# FlightController.net
KiCad netlist of a schematic drawn in Altium Designer
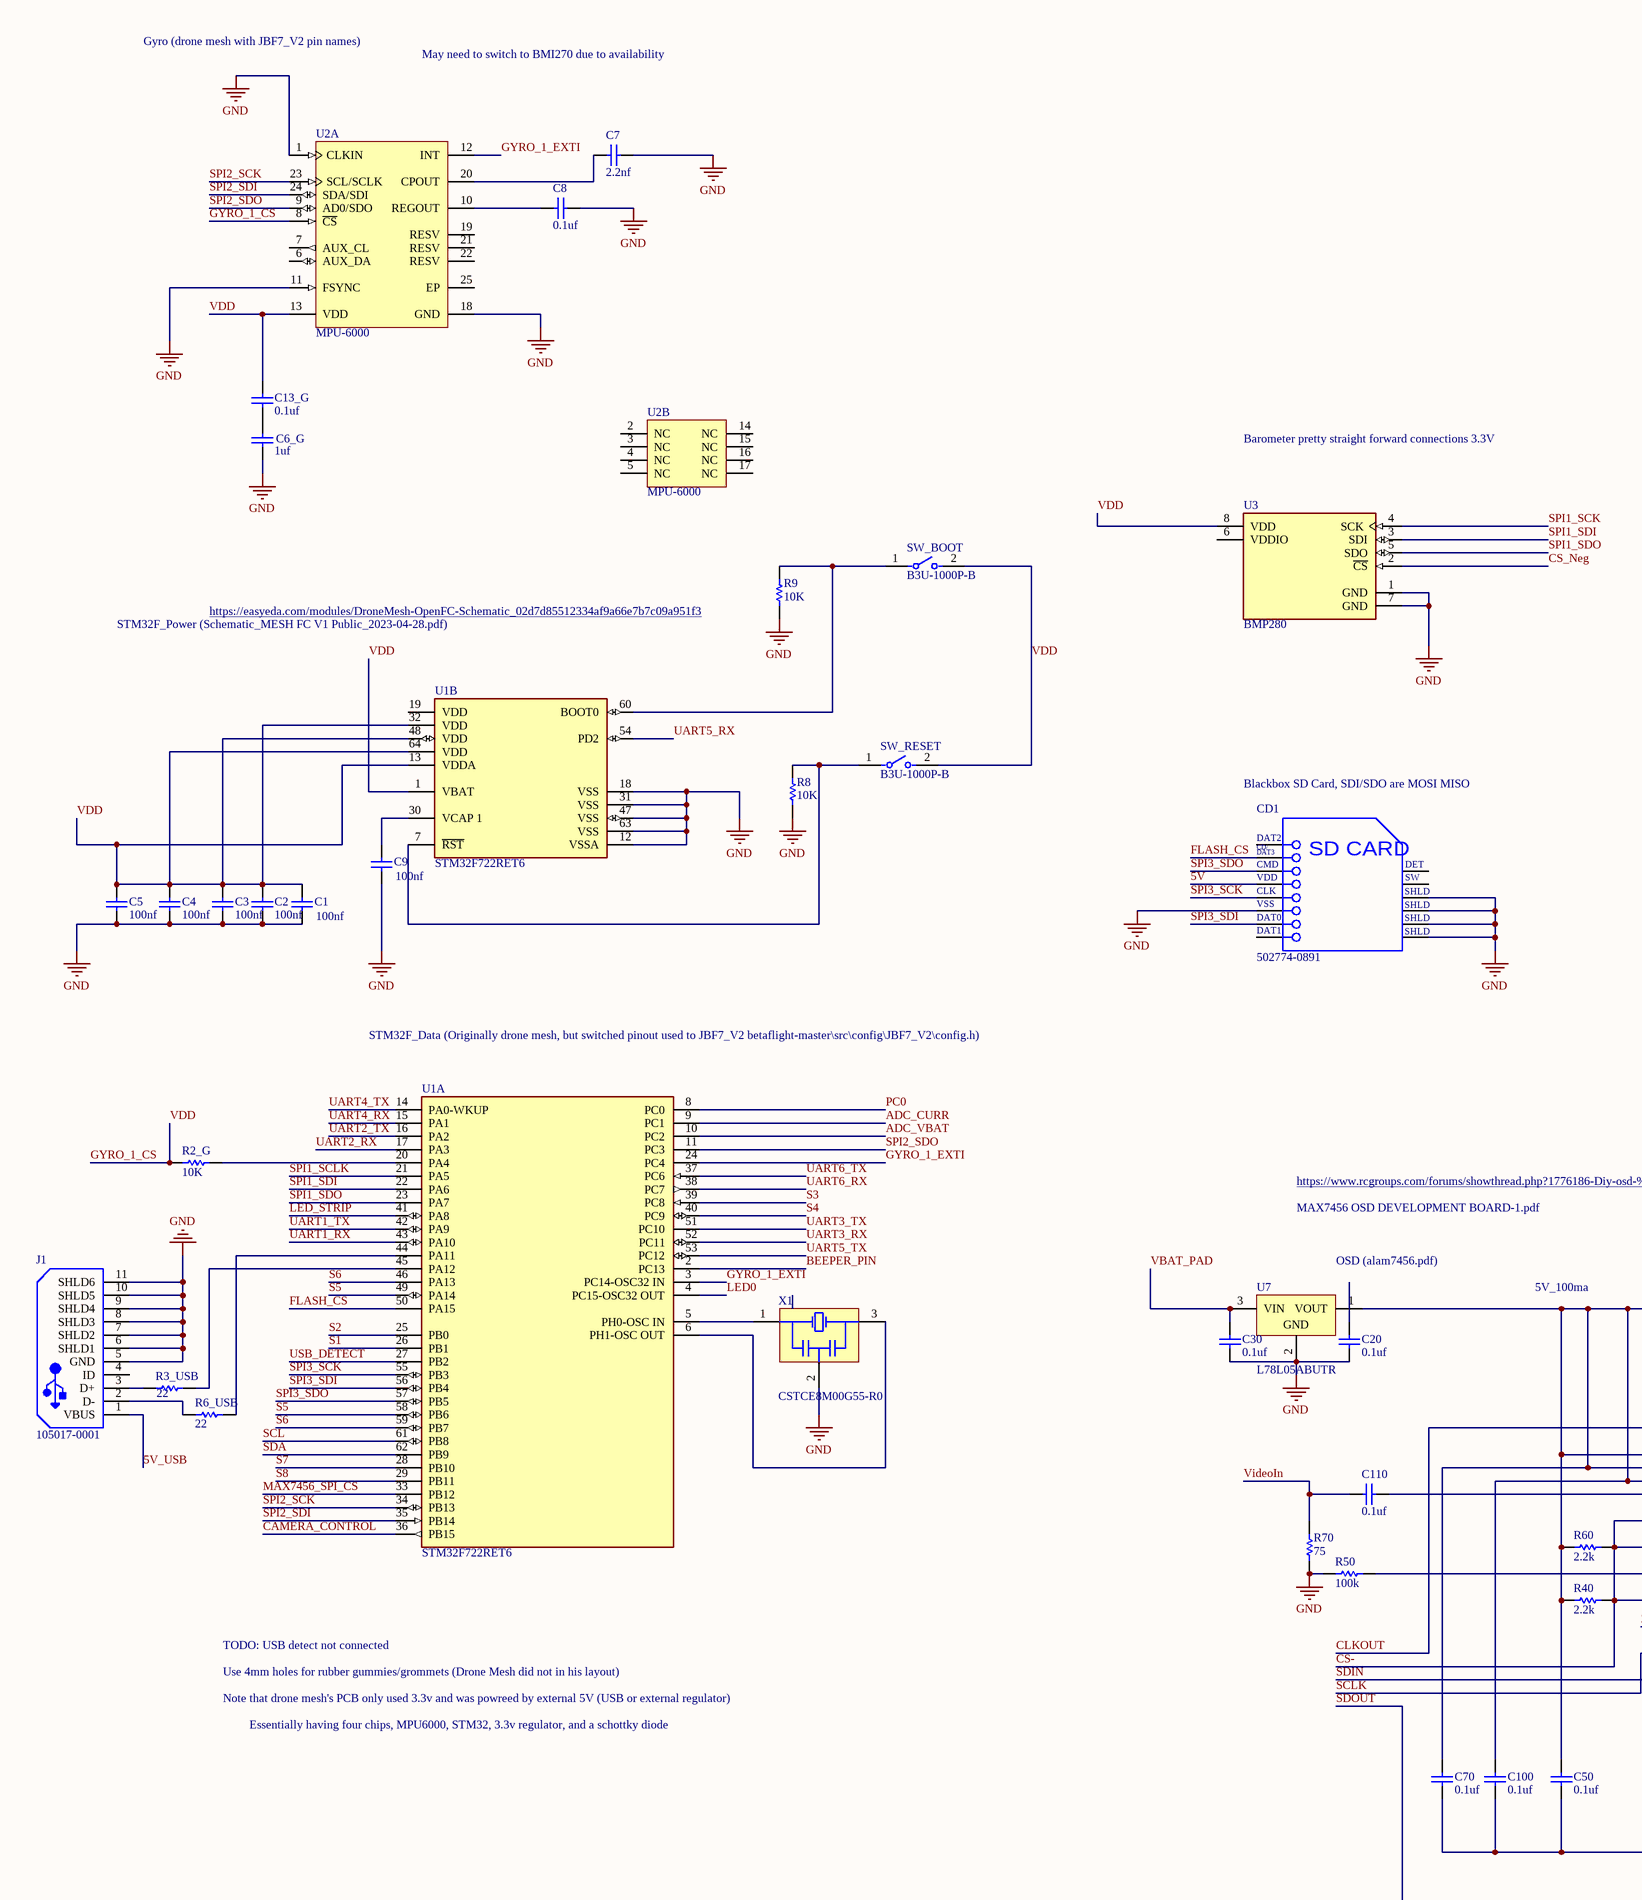
[diagram p0: FlightController.SchDoc, left]
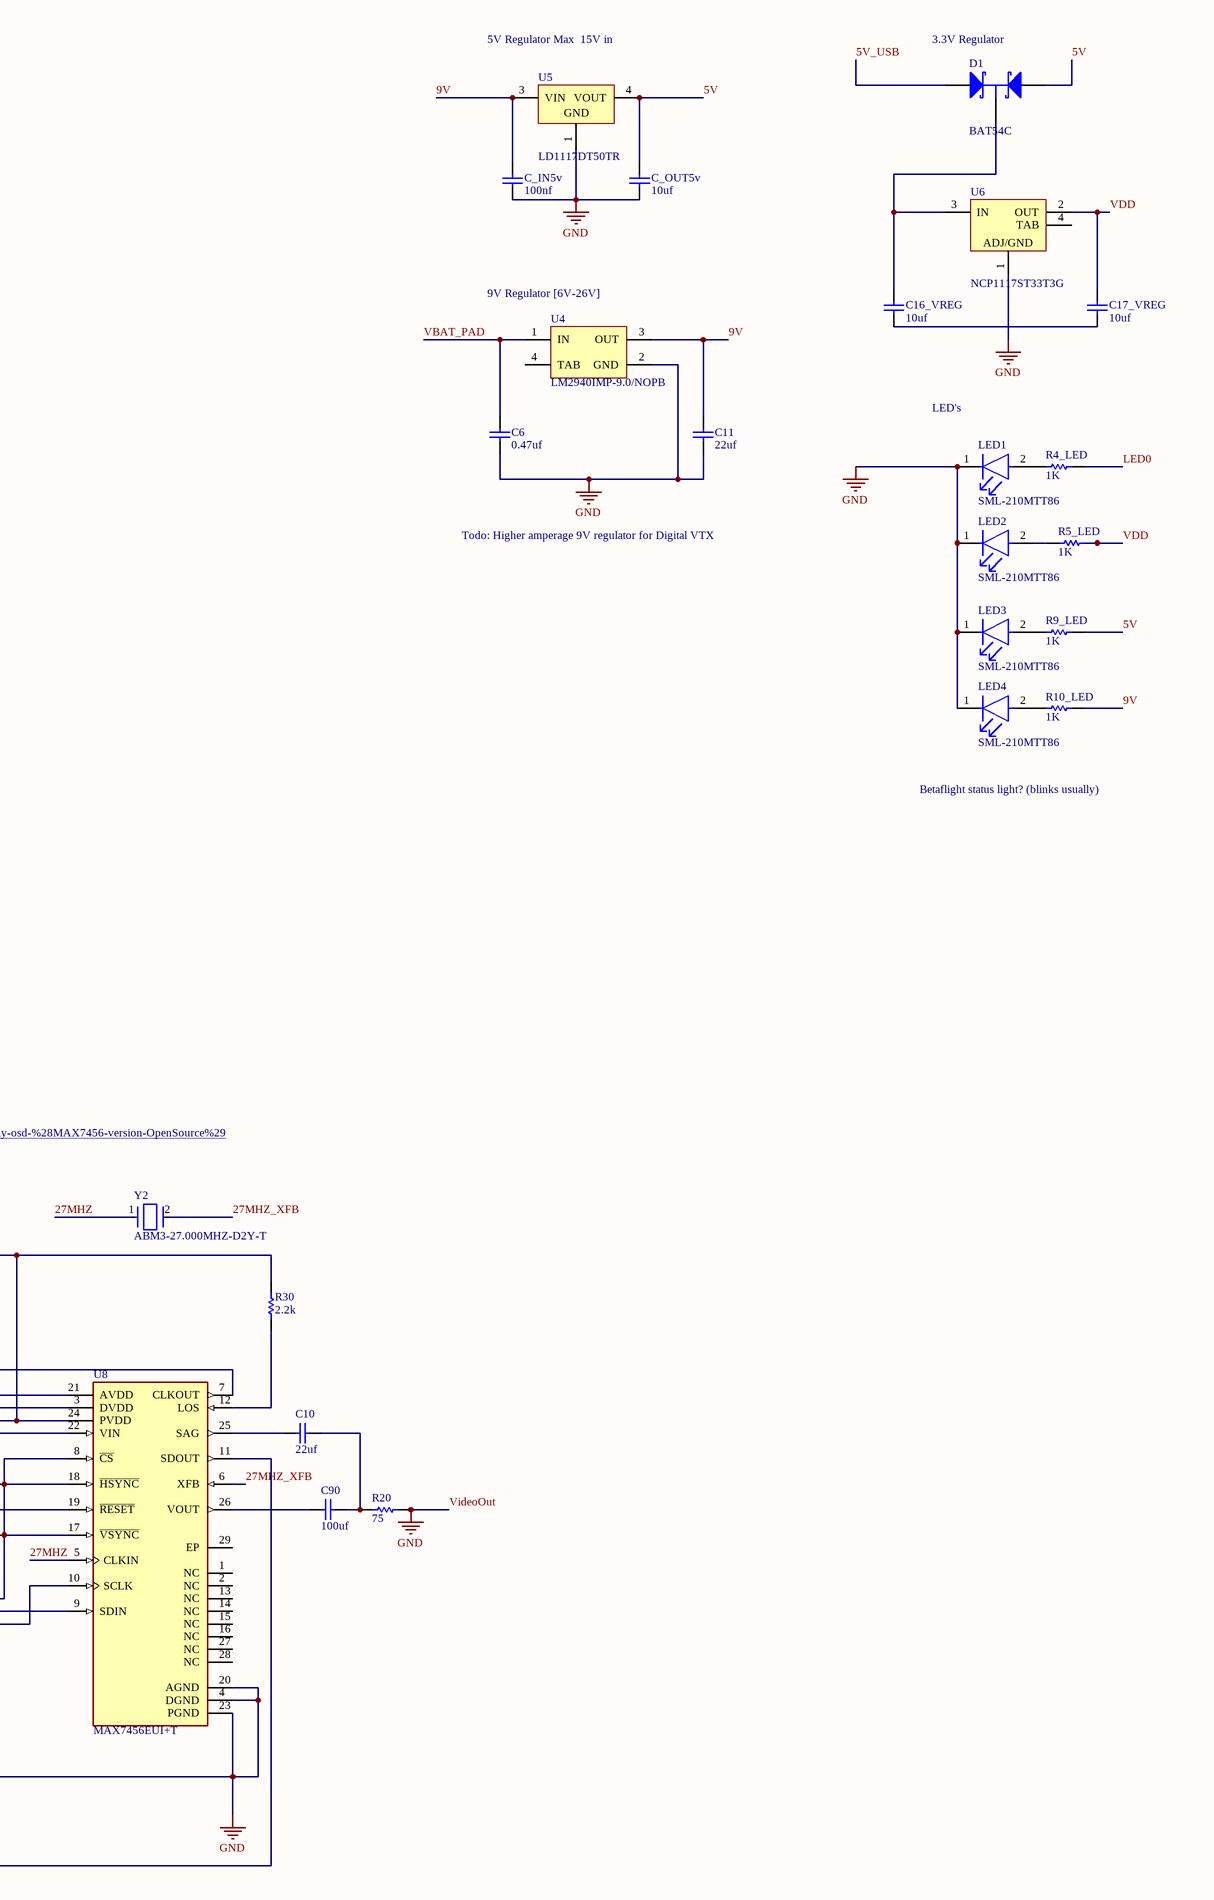
[diagram p1: FlightController.SchDoc, right]

(export (version "E")
  (design (tool "Eeschema 10.0.6"))
  (components
    (comp (ref "C1")
      (value "100nf")
      (footprint "0805")
      (description "Capacitor")
      (libsource (lib "Simulation Generic Components") (part "Capacitor"))
    )
    (comp (ref "C2")
      (value "100nf")
      (footprint "0805")
      (description "Capacitor")
      (libsource (lib "Simulation Generic Components") (part "Capacitor"))
    )
    (comp (ref "C3")
      (value "100nf")
      (footprint "0805")
      (description "Capacitor")
      (libsource (lib "Simulation Generic Components") (part "Capacitor"))
    )
    (comp (ref "C4")
      (value "100nf")
      (footprint "0805")
      (description "Capacitor")
      (libsource (lib "Simulation Generic Components") (part "Capacitor"))
    )
    (comp (ref "C5")
      (value "100nf")
      (footprint "0805")
      (description "Capacitor")
      (libsource (lib "Simulation Generic Components") (part "Capacitor"))
    )
    (comp (ref "C6")
      (value "0.47uf")
      (footprint "0805")
      (description "Capacitor")
      (libsource (lib "Simulation Generic Components") (part "Capacitor"))
    )
    (comp (ref "C6_G")
      (value "1uf")
      (footprint "0805")
      (description "Capacitor")
      (libsource (lib "Simulation Generic Components") (part "Capacitor"))
    )
    (comp (ref "C7")
      (value "2.2nf")
      (footprint "0805")
      (description "Capacitor")
      (libsource (lib "Simulation Generic Components") (part "Capacitor"))
    )
    (comp (ref "C8")
      (value "0.1uf")
      (footprint "0805")
      (description "Capacitor")
      (libsource (lib "Simulation Generic Components") (part "Capacitor"))
    )
    (comp (ref "C9")
      (value "100nf")
      (footprint "0805")
      (description "Capacitor")
      (libsource (lib "Simulation Generic Components") (part "Capacitor"))
    )
    (comp (ref "C10")
      (value "22uf")
      (footprint "0805")
      (description "Capacitor")
      (libsource (lib "Simulation Generic Components") (part "Capacitor"))
    )
    (comp (ref "C11")
      (value "22uf")
      (footprint "0805")
      (description "Capacitor")
      (libsource (lib "Simulation Generic Components") (part "Capacitor"))
    )
    (comp (ref "C13_G")
      (value "0.1uf")
      (footprint "0805")
      (description "Capacitor")
      (libsource (lib "Simulation Generic Components") (part "Capacitor"))
    )
    (comp (ref "C16_VREG")
      (value "10uf")
      (footprint "0805")
      (description "Capacitor")
      (libsource (lib "Simulation Generic Components") (part "Capacitor"))
    )
    (comp (ref "C17_VREG")
      (value "10uf")
      (footprint "0805")
      (description "Capacitor")
      (libsource (lib "Simulation Generic Components") (part "Capacitor"))
    )
    (comp (ref "C20")
      (value "0.1uf")
      (footprint "0805")
      (description "Capacitor")
      (libsource (lib "Simulation Generic Components") (part "Capacitor"))
    )
    (comp (ref "C30")
      (value "0.1uf")
      (footprint "0805")
      (description "Capacitor")
      (libsource (lib "Simulation Generic Components") (part "Capacitor"))
    )
    (comp (ref "C50")
      (value "0.1uf")
      (footprint "0805")
      (description "Capacitor")
      (libsource (lib "Simulation Generic Components") (part "Capacitor"))
    )
    (comp (ref "C70")
      (value "0.1uf")
      (footprint "0805")
      (description "Capacitor")
      (libsource (lib "Simulation Generic Components") (part "Capacitor"))
    )
    (comp (ref "C90")
      (value "100uf")
      (footprint "0805")
      (description "Capacitor")
      (libsource (lib "Simulation Generic Components") (part "Capacitor"))
    )
    (comp (ref "C100")
      (value "0.1uf")
      (footprint "0805")
      (description "Capacitor")
      (libsource (lib "Simulation Generic Components") (part "Capacitor"))
    )
    (comp (ref "C110")
      (value "0.1uf")
      (footprint "0805")
      (description "Capacitor")
      (libsource (lib "Simulation Generic Components") (part "Capacitor"))
    )
    (comp (ref "CD1")
      (value "502774-0891")
      (footprint "MOLX-502774-0891_V")
      (description "Micro SD Memory Card Connector, 0.5 A, 10 V (DC), -25 to 85 degC, 8-Pin SMT, RoHS, Tape and Reel")
      (fields (field (name "MANUFACTURER") "Molex"))
      (libsource (lib "Altium Content Vault") (part "CN-SD-8-2SW-4S_B"))
    )
    (comp (ref "C_IN5v")
      (value "100nf")
      (footprint "0805")
      (description "Capacitor")
      (libsource (lib "Simulation Generic Components") (part "Capacitor"))
    )
    (comp (ref "C_OUT5v")
      (value "10uf")
      (footprint "0805")
      (description "Capacitor")
      (libsource (lib "Simulation Generic Components") (part "Capacitor"))
    )
    (comp (ref "D1")
      (value "BAT54C")
      (footprint "NXP-SOT23-3_V")
      (description "Schottky Barrier Diode, 30 V, 2 uA, -55 to 150 degC, 3-Pin SOT23, RoHS, Tape and Reel")
      (fields (field (name "MANUFACTURER") "NXP Semiconductors"))
      (libsource (lib "Altium Content Vault") (part "NXP-DSKY_A1A2K3-3"))
    )
    (comp (ref "J1")
      (value "105017-0001")
      (footprint "USB-MICRO-B_V")
      (fields (field (name "MANUFACTURER") "Molex"))
      (libsource (lib "Altium Content Vault") (part "USB-5-6SHLD"))
    )
    (comp (ref "LED1")
      (value "SML-210MTT86")
      (footprint "FP-SML-210-MFG")
      (description "LED GREEN CLEAR 0805 SMD")
      (fields
        (field (name "MANUFACTURER") "ROHM")
        (field (name "OCTOPART") "https://octopart.com/sml-210mtt86-rohm-550711")
      )
      (libsource (lib "Altium Content Vault") (part "8706943c75ba83719d021d2fdc84c58"))
    )
    (comp (ref "LED2")
      (value "SML-210MTT86")
      (footprint "FP-SML-210-MFG")
      (description "LED GREEN CLEAR 0805 SMD")
      (fields
        (field (name "MANUFACTURER") "ROHM")
        (field (name "OCTOPART") "https://octopart.com/sml-210mtt86-rohm-550711")
      )
      (libsource (lib "Altium Content Vault") (part "8706943c75ba83719d021d2fdc84c58"))
    )
    (comp (ref "LED3")
      (value "SML-210MTT86")
      (footprint "FP-SML-210-MFG")
      (description "LED GREEN CLEAR 0805 SMD")
      (fields
        (field (name "MANUFACTURER") "ROHM")
        (field (name "OCTOPART") "https://octopart.com/sml-210mtt86-rohm-550711")
      )
      (libsource (lib "Altium Content Vault") (part "8706943c75ba83719d021d2fdc84c58"))
    )
    (comp (ref "LED4")
      (value "SML-210MTT86")
      (footprint "FP-SML-210-MFG")
      (description "LED GREEN CLEAR 0805 SMD")
      (fields
        (field (name "MANUFACTURER") "ROHM")
        (field (name "OCTOPART") "https://octopart.com/sml-210mtt86-rohm-550711")
      )
      (libsource (lib "Altium Content Vault") (part "8706943c75ba83719d021d2fdc84c58"))
    )
    (comp (ref "R2_G")
      (value "10K")
      (footprint "0402")
      (description "Resistor")
      (libsource (lib "Simulation Generic Components") (part "Resistor"))
    )
    (comp (ref "R3_USB")
      (value "22")
      (footprint "0402")
      (description "Resistor")
      (libsource (lib "Simulation Generic Components") (part "Resistor"))
    )
    (comp (ref "R4_LED")
      (value "1K")
      (footprint "0402")
      (description "Resistor")
      (libsource (lib "Simulation Generic Components") (part "Resistor"))
    )
    (comp (ref "R5_LED")
      (value "1K")
      (footprint "0402")
      (description "Resistor")
      (libsource (lib "Simulation Generic Components") (part "Resistor"))
    )
    (comp (ref "R6_USB")
      (value "22")
      (footprint "0402")
      (description "Resistor")
      (libsource (lib "Simulation Generic Components") (part "Resistor"))
    )
    (comp (ref "R8")
      (value "10K")
      (footprint "0402")
      (description "Resistor")
      (libsource (lib "Simulation Generic Components") (part "Resistor"))
    )
    (comp (ref "R9")
      (value "10K")
      (footprint "0402")
      (description "Resistor")
      (libsource (lib "Simulation Generic Components") (part "Resistor"))
    )
    (comp (ref "R9_LED")
      (value "1K")
      (footprint "0402")
      (description "Resistor")
      (libsource (lib "Simulation Generic Components") (part "Resistor"))
    )
    (comp (ref "R10_LED")
      (value "1K")
      (footprint "0402")
      (description "Resistor")
      (libsource (lib "Simulation Generic Components") (part "Resistor"))
    )
    (comp (ref "R20")
      (value "75")
      (footprint "0402")
      (description "Resistor")
      (libsource (lib "Simulation Generic Components") (part "Resistor"))
    )
    (comp (ref "R30")
      (value "2.2k")
      (footprint "0402")
      (description "Resistor")
      (libsource (lib "Simulation Generic Components") (part "Resistor"))
    )
    (comp (ref "R40")
      (value "2.2k")
      (footprint "0402")
      (description "Resistor")
      (libsource (lib "Simulation Generic Components") (part "Resistor"))
    )
    (comp (ref "R50")
      (value "100k")
      (footprint "0402")
      (description "Resistor")
      (libsource (lib "Simulation Generic Components") (part "Resistor"))
    )
    (comp (ref "R60")
      (value "2.2k")
      (footprint "0402")
      (description "Resistor")
      (libsource (lib "Simulation Generic Components") (part "Resistor"))
    )
    (comp (ref "R70")
      (value "75")
      (footprint "0402")
      (description "Resistor")
      (libsource (lib "Simulation Generic Components") (part "Resistor"))
    )
    (comp (ref "SW_BOOT")
      (value "B3U-1000P-B")
      (footprint "FP-B3U-1000P-B-MFG")
      (description "Tactile Switch SPST-NO Top Actuated Surface Mount")
      (fields (field (name "OCTOPART") "https://octopart.com/b3u-1000p-b-omron-1057356"))
      (libsource (lib "Altium Content Vault") (part "bb27bde45df87f1f469753f287ef5ae"))
    )
    (comp (ref "SW_RESET")
      (value "B3U-1000P-B")
      (footprint "FP-B3U-1000P-B-MFG")
      (description "Tactile Switch SPST-NO Top Actuated Surface Mount")
      (fields (field (name "OCTOPART") "https://octopart.com/b3u-1000p-b-omron-1057356"))
      (libsource (lib "Altium Content Vault") (part "bb27bde45df87f1f469753f287ef5ae"))
    )
    (comp (ref "U1")
      (value "STM32F722RET6")
      (footprint "FP-LQFP64-5W-IPC_A")
      (description "IC MCU 32BIT 512KB FLASH 64LQFP")
      (libsource (lib "Altium Content Vault") (part "413d838e29415566e97646d24ea8a00"))
    )
    (comp (ref "U2")
      (value "MPU-6000")
      (footprint "INSE-QFN-24_V")
      (fields (field (name "MANUFACTURER") "InvenSense"))
      (libsource (lib "Altium Content Vault") (part "INSE-MPU-6000"))
    )
    (comp (ref "U3")
      (value "BMP280")
      (footprint "FP-BMP280-MFG")
      (description "SENSOR PRESSURE ABS")
      (libsource (lib "Altium Content Vault") (part "69b1aacbb03d82763a43fac02afba64"))
    )
    (comp (ref "U4")
      (value "LM2940IMP-9.0/NOPB")
      (footprint "DCY0004A_L")
      (description "1A Low Dropout Regulator, 4-pin SOT-223, Pb-Free")
      (fields (field (name "MANUFACTURER") "Texas Instruments"))
      (libsource (lib "Altium Content Vault") (part "PM-REG-LM2940-TO4"))
    )
    (comp (ref "U5")
      (value "LD1117DT50TR")
      (footprint "TO-252_N")
      (description "Fixed Low Drop Positive Voltage Regulator, 5V, 3-Pin DPAK, Tape and Reel")
      (libsource (lib "Altium Content Vault") (part "PM-REG-LD1117-SOT3"))
    )
    (comp (ref "U6")
      (value "NCP1117ST33T3G")
      (footprint "ONSC-SOT-223-4-318H-01_A_V")
      (fields (field (name "TOLERANCE") "1%"))
      (libsource (lib "Altium Content Vault") (part "ONSC-NCP1117-SOT223-4"))
    )
    (comp (ref "U7")
      (value "L78L05ABUTR")
      (footprint "SOT-89_N")
      (description "Positive Voltage Regulator, 5V, 4-Pin SOT-89, Tape and Reel")
      (libsource (lib "Altium Content Vault") (part "PM-REG-7805-SIL3"))
    )
    (comp (ref "U8")
      (value "MAX7456EUI+T")
      (footprint "FP-U28E-5-MFG")
      (description "IC DISPLAY 1CH W/EEPROM 28TSSOP")
      (fields
        (field (name "OCTOPART") "https://octopart.com/max7456eui%2Bt-maxim+integrated-42626431")
        (field (name "OBSOLETE PART") "true")
      )
      (libsource (lib "Altium Content Vault") (part "41ca4868ea377862c641f4b23eb8cbf"))
    )
    (comp (ref "X1")
      (value "CSTCE8M00G55-R0")
      (footprint "MURA-CSTCE_G_A-3_V")
      (description "Ceramic Resonator, 8 MHz, +/- 0.5%, -20 to 80 degC, 3-Pin SMD, RoHS, Tape and Reel")
      (fields (field (name "TOLERANCE") "0.5%") (field (name "MANUFACTURER") "Murata"))
      (libsource (lib "Altium Content Vault") (part "MURA-CSTCE_G_A-3"))
    )
    (comp (ref "Y2")
      (value "ABM3-27.000MHZ-D2Y-T")
      (footprint "FP-ABM3-MFG")
      (description "Crystal 27MHz ±20ppm 18pF SMD-2 5mm x 3.2mm")
      (fields (field (name "TOLERANCE") "20ppm"))
      (libsource (lib "Altium Content Vault") (part "c23a69dc6c9e2f18f2079038eb95dd1"))
    )
  )
  (nets
    (net (code "1") (name "/5V") (class "Default")
      (node (ref "CD1") (pin "4") (pinfunction "VDD_4") (pintype "passive"))
      (node (ref "C_OUT5v") (pin "2") (pinfunction "2_2") (pintype "passive"))
      (node (ref "D1") (pin "1") (pinfunction "A_1") (pintype "passive"))
      (node (ref "R9_LED") (pin "2") (pinfunction "2_2") (pintype "passive"))
      (node (ref "U5") (pin "4") (pinfunction "VOUT_4") (pintype "power_in"))
    )
    (net (code "2") (name "/5V_USB") (class "Default")
      (node (ref "D1") (pin "2") (pinfunction "A_2") (pintype "passive"))
      (node (ref "J1") (pin "1") (pinfunction "VBUS_1") (pintype "passive"))
    )
    (net (code "3") (name "/9V") (class "Default")
      (node (ref "C11") (pin "2") (pinfunction "2_2") (pintype "passive"))
      (node (ref "C_IN5v") (pin "2") (pinfunction "2_2") (pintype "passive"))
      (node (ref "R10_LED") (pin "2") (pinfunction "2_2") (pintype "passive"))
      (node (ref "U4") (pin "3") (pinfunction "OUT_3") (pintype "power_in"))
      (node (ref "U5") (pin "3") (pinfunction "VIN_3") (pintype "power_in"))
    )
    (net (code "4") (name "/27MHZ") (class "Default")
      (node (ref "U8") (pin "5") (pinfunction "CLKIN_5") (pintype "input"))
      (node (ref "Y2") (pin "1") (pinfunction "1_1") (pintype "passive"))
    )
    (net (code "5") (name "/27MHZ_XFB") (class "Default")
      (node (ref "U8") (pin "6") (pinfunction "XFB_6") (pintype "input"))
      (node (ref "Y2") (pin "2") (pinfunction "2_2") (pintype "passive"))
    )
    (net (code "6") (name "/ADC_CURR") (class "Default")
      (node (ref "U1") (pin "9") (pinfunction "PC1_9") (pintype "passive"))
    )
    (net (code "7") (name "/ADC_VBAT") (class "Default")
      (node (ref "U1") (pin "10") (pinfunction "PC2_10") (pintype "passive"))
    )
    (net (code "8") (name "/BEEPER_PIN") (class "Default")
      (node (ref "U1") (pin "2") (pinfunction "PC13_2") (pintype "passive"))
    )
    (net (code "9") (name "/CAMERA_CONTROL") (class "Default")
      (node (ref "U1") (pin "36") (pinfunction "PB15_36") (pintype "output"))
    )
    (net (code "10") (name "/CLKOUT") (class "Default")
      (node (ref "U8") (pin "7") (pinfunction "CLKOUT_7") (pintype "output"))
    )
    (net (code "11") (name "/CS-") (class "Default")
      (node (ref "R40") (pin "1") (pinfunction "1_1") (pintype "passive"))
      (node (ref "R60") (pin "1") (pinfunction "1_1") (pintype "passive"))
      (node (ref "U8") (pin "17") (pinfunction "~{VSYNC}_17") (pintype "input"))
      (node (ref "U8") (pin "18") (pinfunction "~{HSYNC}_18") (pintype "input"))
      (node (ref "U8") (pin "8") (pinfunction "~{CS}_8") (pintype "input"))
    )
    (net (code "12") (name "/CS_Neg") (class "Default")
      (node (ref "U3") (pin "2") (pinfunction "~{CS}_2") (pintype "input"))
    )
    (net (code "13") (name "/FLASH_CS") (class "Default")
      (node (ref "CD1") (pin "2") (pinfunction "CD/DAT3_2") (pintype "passive"))
      (node (ref "U1") (pin "50") (pinfunction "PA15_50") (pintype "power_in"))
    )
    (net (code "14") (name "/GYRO_1_CS") (class "Default")
      (node (ref "C1") (pin "2") (pinfunction "2_2") (pintype "passive"))
      (node (ref "C13_G") (pin "2") (pinfunction "2_2") (pintype "passive"))
      (node (ref "C17_VREG") (pin "2") (pinfunction "2_2") (pintype "passive"))
      (node (ref "C2") (pin "2") (pinfunction "2_2") (pintype "passive"))
      (node (ref "C3") (pin "2") (pinfunction "2_2") (pintype "passive"))
      (node (ref "C4") (pin "2") (pinfunction "2_2") (pintype "passive"))
      (node (ref "C5") (pin "2") (pinfunction "2_2") (pintype "passive"))
      (node (ref "R2_G") (pin "1") (pinfunction "1_1") (pintype "passive"))
      (node (ref "R5_LED") (pin "2") (pinfunction "2_2") (pintype "passive"))
      (node (ref "SW_BOOT") (pin "2") (pinfunction "2_2") (pintype "passive"))
      (node (ref "SW_RESET") (pin "2") (pinfunction "2_2") (pintype "passive"))
      (node (ref "U1") (pin "1") (pinfunction "VBAT_1") (pintype "passive"))
      (node (ref "U1") (pin "13") (pinfunction "VDDA_13") (pintype "passive"))
      (node (ref "U1") (pin "32") (pinfunction "VDD_32") (pintype "passive"))
      (node (ref "U1") (pin "48") (pinfunction "VDD_48") (pintype "bidirectional"))
      (node (ref "U1") (pin "64") (pinfunction "VDD_64") (pintype "power_in"))
      (node (ref "U2") (pin "13") (pinfunction "VDD_13") (pintype "power_in"))
      (node (ref "U2") (pin "8") (pinfunction "~{CS}_8") (pintype "input"))
      (node (ref "U3") (pin "8") (pinfunction "VDD_8") (pintype "power_in"))
      (node (ref "U6") (pin "2") (pinfunction "OUT_2") (pintype "power_in"))
    )
    (net (code "15") (name "/GYRO_1_EXTI") (class "Default")
      (node (ref "U1") (pin "24") (pinfunction "PC4_24") (pintype "passive"))
      (node (ref "U1") (pin "3") (pinfunction "PC14-OSC32_IN_3") (pintype "passive"))
      (node (ref "U2") (pin "12") (pinfunction "INT_12") (pintype "open_collector"))
    )
    (net (code "16") (name "/LED0") (class "Default")
      (node (ref "R4_LED") (pin "2") (pinfunction "2_2") (pintype "passive"))
      (node (ref "U1") (pin "4") (pinfunction "PC15-OSC32_OUT_4") (pintype "passive"))
    )
    (net (code "17") (name "/LED_STRIP") (class "Default")
      (node (ref "U1") (pin "41") (pinfunction "PA8_41") (pintype "bidirectional"))
    )
    (net (code "18") (name "/MAX7456_SPI_CS") (class "Default")
      (node (ref "U1") (pin "33") (pinfunction "PB12_33") (pintype "power_in"))
    )
    (net (code "19") (name "/PC0") (class "Default")
      (node (ref "U1") (pin "8") (pinfunction "PC0_8") (pintype "passive"))
    )
    (net (code "20") (name "/S1") (class "Default")
      (node (ref "U1") (pin "26") (pinfunction "PB1_26") (pintype "passive"))
    )
    (net (code "21") (name "/S2") (class "Default")
      (node (ref "U1") (pin "25") (pinfunction "PB0_25") (pintype "passive"))
    )
    (net (code "22") (name "/S3") (class "Default")
      (node (ref "U1") (pin "39") (pinfunction "PC8_39") (pintype "input"))
    )
    (net (code "23") (name "/S4") (class "Default")
      (node (ref "U1") (pin "40") (pinfunction "PC9_40") (pintype "bidirectional"))
    )
    (net (code "24") (name "/S5") (class "Default")
      (node (ref "U1") (pin "49") (pinfunction "PA14_49") (pintype "bidirectional"))
      (node (ref "U1") (pin "58") (pinfunction "PB6_58") (pintype "bidirectional"))
    )
    (net (code "25") (name "/S6") (class "Default")
      (node (ref "U1") (pin "46") (pinfunction "PA13_46") (pintype "passive"))
      (node (ref "U1") (pin "59") (pinfunction "PB7_59") (pintype "bidirectional"))
    )
    (net (code "26") (name "/S7") (class "Default")
      (node (ref "U1") (pin "28") (pinfunction "PB10_28") (pintype "passive"))
    )
    (net (code "27") (name "/S8") (class "Default")
      (node (ref "U1") (pin "29") (pinfunction "PB11_29") (pintype "passive"))
    )
    (net (code "28") (name "/SCL") (class "Default")
      (node (ref "U1") (pin "61") (pinfunction "PB8_61") (pintype "bidirectional"))
    )
    (net (code "29") (name "/SCLK") (class "Default")
      (node (ref "U8") (pin "10") (pinfunction "SCLK_10") (pintype "input"))
    )
    (net (code "30") (name "/SDA") (class "Default")
      (node (ref "U1") (pin "62") (pinfunction "PB9_62") (pintype "power_in"))
    )
    (net (code "31") (name "/SDIN") (class "Default")
      (node (ref "U8") (pin "9") (pinfunction "SDIN_9") (pintype "input"))
    )
    (net (code "32") (name "/SDOUT") (class "Default")
      (node (ref "U8") (pin "11") (pinfunction "SDOUT_11") (pintype "output"))
    )
    (net (code "33") (name "/SPI1_SCK") (class "Default")
      (node (ref "U3") (pin "4") (pinfunction "SCK_4") (pintype "input"))
    )
    (net (code "34") (name "/SPI1_SCLK") (class "Default")
      (node (ref "U1") (pin "21") (pinfunction "PA5_21") (pintype "passive"))
    )
    (net (code "35") (name "/SPI1_SDI") (class "Default")
      (node (ref "U1") (pin "22") (pinfunction "PA6_22") (pintype "passive"))
      (node (ref "U3") (pin "3") (pinfunction "SDI_3") (pintype "bidirectional"))
    )
    (net (code "36") (name "/SPI1_SDO") (class "Default")
      (node (ref "U1") (pin "23") (pinfunction "PA7_23") (pintype "passive"))
      (node (ref "U3") (pin "5") (pinfunction "SDO_5") (pintype "bidirectional"))
    )
    (net (code "37") (name "/SPI2_SCK") (class "Default")
      (node (ref "U1") (pin "34") (pinfunction "PB13_34") (pintype "bidirectional"))
      (node (ref "U2") (pin "23") (pinfunction "SCL/SCLK_23") (pintype "input"))
    )
    (net (code "38") (name "/SPI2_SDI") (class "Default")
      (node (ref "U1") (pin "35") (pinfunction "PB14_35") (pintype "input"))
      (node (ref "U2") (pin "24") (pinfunction "SDA/SDI_24") (pintype "bidirectional"))
    )
    (net (code "39") (name "/SPI2_SDO") (class "Default")
      (node (ref "U1") (pin "11") (pinfunction "PC3_11") (pintype "passive"))
      (node (ref "U2") (pin "9") (pinfunction "AD0/SDO_9") (pintype "bidirectional"))
    )
    (net (code "40") (name "/SPI3_SCK") (class "Default")
      (node (ref "CD1") (pin "5") (pinfunction "CLK_5") (pintype "passive"))
      (node (ref "U1") (pin "55") (pinfunction "PB3_55") (pintype "bidirectional"))
    )
    (net (code "41") (name "/SPI3_SDI") (class "Default")
      (node (ref "CD1") (pin "7") (pinfunction "DAT0_7") (pintype "passive"))
      (node (ref "U1") (pin "56") (pinfunction "PB4_56") (pintype "bidirectional"))
    )
    (net (code "42") (name "/SPI3_SDO") (class "Default")
      (node (ref "CD1") (pin "3") (pinfunction "CMD_3") (pintype "passive"))
      (node (ref "U1") (pin "57") (pinfunction "PB5_57") (pintype "bidirectional"))
    )
    (net (code "43") (name "/UART1_RX") (class "Default")
      (node (ref "U1") (pin "43") (pinfunction "PA10_43") (pintype "bidirectional"))
    )
    (net (code "44") (name "/UART1_TX") (class "Default")
      (node (ref "U1") (pin "42") (pinfunction "PA9_42") (pintype "bidirectional"))
    )
    (net (code "45") (name "/UART2_RX") (class "Default")
      (node (ref "U1") (pin "17") (pinfunction "PA3_17") (pintype "passive"))
    )
    (net (code "46") (name "/UART2_TX") (class "Default")
      (node (ref "U1") (pin "16") (pinfunction "PA2_16") (pintype "passive"))
    )
    (net (code "47") (name "/UART3_RX") (class "Default")
      (node (ref "U1") (pin "52") (pinfunction "PC11_52") (pintype "bidirectional"))
    )
    (net (code "48") (name "/UART3_TX") (class "Default")
      (node (ref "U1") (pin "51") (pinfunction "PC10_51") (pintype "power_in"))
    )
    (net (code "49") (name "/UART4_RX") (class "Default")
      (node (ref "U1") (pin "15") (pinfunction "PA1_15") (pintype "passive"))
    )
    (net (code "50") (name "/UART4_TX") (class "Default")
      (node (ref "U1") (pin "14") (pinfunction "PA0-WKUP_14") (pintype "passive"))
    )
    (net (code "51") (name "/UART5_RX") (class "Default")
      (node (ref "U1") (pin "54") (pinfunction "PD2_54") (pintype "bidirectional"))
    )
    (net (code "52") (name "/UART5_TX") (class "Default")
      (node (ref "U1") (pin "53") (pinfunction "PC12_53") (pintype "bidirectional"))
    )
    (net (code "53") (name "/UART6_RX") (class "Default")
      (node (ref "U1") (pin "38") (pinfunction "PC7_38") (pintype "output"))
    )
    (net (code "54") (name "/UART6_TX") (class "Default")
      (node (ref "U1") (pin "37") (pinfunction "PC6_37") (pintype "input"))
    )
    (net (code "55") (name "/USB_DETECT") (class "Default")
      (node (ref "U1") (pin "27") (pinfunction "PB2_27") (pintype "passive"))
    )
    (net (code "56") (name "/VBAT_PAD") (class "Default")
      (node (ref "C30") (pin "1") (pinfunction "1_1") (pintype "passive"))
      (node (ref "C6") (pin "2") (pinfunction "2_2") (pintype "passive"))
      (node (ref "U4") (pin "1") (pinfunction "IN_1") (pintype "power_in"))
      (node (ref "U7") (pin "3") (pinfunction "VIN_3") (pintype "power_in"))
    )
    (net (code "57") (name "/VideoIn") (class "Default")
      (node (ref "C110") (pin "2") (pinfunction "2_2") (pintype "passive"))
      (node (ref "R70") (pin "2") (pinfunction "2_2") (pintype "passive"))
    )
    (net (code "58") (name "GND") (class "Default")
      (node (ref "C1") (pin "1") (pinfunction "1_1") (pintype "passive"))
      (node (ref "C100") (pin "1") (pinfunction "1_1") (pintype "passive"))
      (node (ref "C11") (pin "1") (pinfunction "1_1") (pintype "passive"))
      (node (ref "C2") (pin "1") (pinfunction "1_1") (pintype "passive"))
      (node (ref "C20") (pin "2") (pinfunction "2_2") (pintype "passive"))
      (node (ref "C3") (pin "1") (pinfunction "1_1") (pintype "passive"))
      (node (ref "C30") (pin "2") (pinfunction "2_2") (pintype "passive"))
      (node (ref "C4") (pin "1") (pinfunction "1_1") (pintype "passive"))
      (node (ref "C5") (pin "1") (pinfunction "1_1") (pintype "passive"))
      (node (ref "C50") (pin "1") (pinfunction "1_1") (pintype "passive"))
      (node (ref "C6") (pin "1") (pinfunction "1_1") (pintype "passive"))
      (node (ref "C6_G") (pin "1") (pinfunction "1_1") (pintype "passive"))
      (node (ref "C7") (pin "2") (pinfunction "2_2") (pintype "passive"))
      (node (ref "C70") (pin "1") (pinfunction "1_1") (pintype "passive"))
      (node (ref "C8") (pin "2") (pinfunction "2_2") (pintype "passive"))
      (node (ref "C9") (pin "1") (pinfunction "1_1") (pintype "passive"))
      (node (ref "CD1") (pin "11") (pinfunction "SHLD_11") (pintype "passive"))
      (node (ref "CD1") (pin "12") (pinfunction "SHLD_12") (pintype "passive"))
      (node (ref "CD1") (pin "13") (pinfunction "SHLD_13") (pintype "passive"))
      (node (ref "CD1") (pin "14") (pinfunction "SHLD_14") (pintype "passive"))
      (node (ref "CD1") (pin "6") (pinfunction "VSS_6") (pintype "passive"))
      (node (ref "C_IN5v") (pin "1") (pinfunction "1_1") (pintype "passive"))
      (node (ref "C_OUT5v") (pin "1") (pinfunction "1_1") (pintype "passive"))
      (node (ref "J1") (pin "10") (pinfunction "SHLD5_10") (pintype "passive"))
      (node (ref "J1") (pin "11") (pinfunction "SHLD6_11") (pintype "passive"))
      (node (ref "J1") (pin "5") (pinfunction "GND_5") (pintype "passive"))
      (node (ref "J1") (pin "6") (pinfunction "SHLD1_6") (pintype "passive"))
      (node (ref "J1") (pin "7") (pinfunction "SHLD2_7") (pintype "passive"))
      (node (ref "J1") (pin "8") (pinfunction "SHLD3_8") (pintype "passive"))
      (node (ref "J1") (pin "9") (pinfunction "SHLD4_9") (pintype "passive"))
      (node (ref "LED1") (pin "1") (pinfunction "C_1") (pintype "passive"))
      (node (ref "LED2") (pin "1") (pinfunction "C_1") (pintype "passive"))
      (node (ref "LED3") (pin "1") (pinfunction "C_1") (pintype "passive"))
      (node (ref "LED4") (pin "1") (pinfunction "C_1") (pintype "passive"))
      (node (ref "R20") (pin "2") (pinfunction "2_2") (pintype "passive"))
      (node (ref "R50") (pin "2") (pinfunction "2_2") (pintype "passive"))
      (node (ref "R70") (pin "1") (pinfunction "1_1") (pintype "passive"))
      (node (ref "R8") (pin "1") (pinfunction "1_1") (pintype "passive"))
      (node (ref "R9") (pin "1") (pinfunction "1_1") (pintype "passive"))
      (node (ref "U1") (pin "12") (pinfunction "VSSA_12") (pintype "passive"))
      (node (ref "U1") (pin "18") (pinfunction "VSS_18") (pintype "passive"))
      (node (ref "U1") (pin "31") (pinfunction "VSS_31") (pintype "passive"))
      (node (ref "U1") (pin "47") (pinfunction "VSS_47") (pintype "bidirectional"))
      (node (ref "U1") (pin "63") (pinfunction "VSS_63") (pintype "power_in"))
      (node (ref "U2") (pin "1") (pinfunction "CLKIN_1") (pintype "input"))
      (node (ref "U2") (pin "11") (pinfunction "FSYNC_11") (pintype "input"))
      (node (ref "U2") (pin "18") (pinfunction "GND_18") (pintype "power_in"))
      (node (ref "U3") (pin "1") (pinfunction "GND_1") (pintype "power_in"))
      (node (ref "U3") (pin "7") (pinfunction "GND_7") (pintype "power_in"))
      (node (ref "U4") (pin "2") (pinfunction "GND_2") (pintype "power_in"))
      (node (ref "U5") (pin "1") (pinfunction "GND_1") (pintype "power_in"))
      (node (ref "U6") (pin "1") (pinfunction "ADJ/GND_1") (pintype "passive"))
      (node (ref "U7") (pin "2") (pinfunction "GND_2") (pintype "power_in"))
      (node (ref "U8") (pin "20") (pinfunction "AGND_20") (pintype "power_in"))
      (node (ref "U8") (pin "23") (pinfunction "PGND_23") (pintype "power_in"))
      (node (ref "U8") (pin "4") (pinfunction "DGND_4") (pintype "power_in"))
      (node (ref "X1") (pin "2") (pinfunction "GND_2") (pintype "power_in"))
    )
    (net (code "59") (name "Net-(C10-Pad2)") (class "Default")
      (node (ref "C10") (pin "2") (pinfunction "2_2") (pintype "passive"))
      (node (ref "C90") (pin "2") (pinfunction "2_2") (pintype "passive"))
      (node (ref "R20") (pin "1") (pinfunction "1_1") (pintype "passive"))
    )
    (net (code "60") (name "Net-(C13_G-Pad1)") (class "Default")
      (node (ref "C13_G") (pin "1") (pinfunction "1_1") (pintype "passive"))
      (node (ref "C6_G") (pin "2") (pinfunction "2_2") (pintype "passive"))
    )
    (net (code "61") (name "Net-(C16_VREG-Pad1)") (class "Default")
      (node (ref "C16_VREG") (pin "1") (pinfunction "1_1") (pintype "passive"))
      (node (ref "C17_VREG") (pin "1") (pinfunction "1_1") (pintype "passive"))
    )
    (net (code "62") (name "Net-(D1-K)") (class "Default")
      (node (ref "C16_VREG") (pin "2") (pinfunction "2_2") (pintype "passive"))
      (node (ref "D1") (pin "3") (pinfunction "K_3") (pintype "passive"))
      (node (ref "U6") (pin "3") (pinfunction "IN_3") (pintype "power_in"))
    )
    (net (code "63") (name "Net-(J1-D+)") (class "Default")
      (node (ref "J1") (pin "3") (pinfunction "D+_3") (pintype "passive"))
      (node (ref "R3_USB") (pin "1") (pinfunction "1_1") (pintype "passive"))
    )
    (net (code "64") (name "Net-(J1-D-)") (class "Default")
      (node (ref "J1") (pin "2") (pinfunction "D-_2") (pintype "passive"))
      (node (ref "R6_USB") (pin "1") (pinfunction "1_1") (pintype "passive"))
    )
    (net (code "65") (name "Net-(LED1-A)") (class "Default")
      (node (ref "LED1") (pin "2") (pinfunction "A_2") (pintype "passive"))
      (node (ref "R4_LED") (pin "1") (pinfunction "1_1") (pintype "passive"))
    )
    (net (code "66") (name "Net-(LED2-A)") (class "Default")
      (node (ref "LED2") (pin "2") (pinfunction "A_2") (pintype "passive"))
      (node (ref "R5_LED") (pin "1") (pinfunction "1_1") (pintype "passive"))
    )
    (net (code "67") (name "Net-(LED3-A)") (class "Default")
      (node (ref "LED3") (pin "2") (pinfunction "A_2") (pintype "passive"))
      (node (ref "R9_LED") (pin "1") (pinfunction "1_1") (pintype "passive"))
    )
    (net (code "68") (name "Net-(LED4-A)") (class "Default")
      (node (ref "LED4") (pin "2") (pinfunction "A_2") (pintype "passive"))
      (node (ref "R10_LED") (pin "1") (pinfunction "1_1") (pintype "passive"))
    )
    (net (code "69") (name "Net-(U1A-PA4)") (class "Default")
      (node (ref "R2_G") (pin "2") (pinfunction "2_2") (pintype "passive"))
      (node (ref "U1") (pin "20") (pinfunction "PA4_20") (pintype "passive"))
    )
    (net (code "70") (name "Net-(U1A-PA11)") (class "Default")
      (node (ref "R6_USB") (pin "2") (pinfunction "2_2") (pintype "passive"))
      (node (ref "U1") (pin "44") (pinfunction "PA11_44") (pintype "power_in"))
    )
    (net (code "71") (name "Net-(U1A-PA12)") (class "Default")
      (node (ref "R3_USB") (pin "2") (pinfunction "2_2") (pintype "passive"))
      (node (ref "U1") (pin "45") (pinfunction "PA12_45") (pintype "power_in"))
    )
    (net (code "72") (name "Net-(U1A-PH0-OSC_IN)") (class "Default")
      (node (ref "U1") (pin "5") (pinfunction "PH0-OSC_IN_5") (pintype "passive"))
      (node (ref "X1") (pin "1") (pinfunction "X1_1") (pintype "passive"))
    )
    (net (code "73") (name "Net-(U1A-PH1-OSC_OUT)") (class "Default")
      (node (ref "U1") (pin "6") (pinfunction "PH1-OSC_OUT_6") (pintype "passive"))
      (node (ref "X1") (pin "3") (pinfunction "X2_3") (pintype "passive"))
    )
    (net (code "74") (name "Net-(U1B-BOOT0)") (class "Default")
      (node (ref "R9") (pin "2") (pinfunction "2_2") (pintype "passive"))
      (node (ref "SW_BOOT") (pin "1") (pinfunction "1_1") (pintype "passive"))
      (node (ref "U1") (pin "60") (pinfunction "BOOT0_60") (pintype "bidirectional"))
    )
    (net (code "75") (name "Net-(U1B-VCAP_1)") (class "Default")
      (node (ref "C9") (pin "2") (pinfunction "2_2") (pintype "passive"))
      (node (ref "U1") (pin "30") (pinfunction "VCAP_1_30") (pintype "passive"))
    )
    (net (code "76") (name "Net-(U1B-~{RST})") (class "Default")
      (node (ref "R8") (pin "2") (pinfunction "2_2") (pintype "passive"))
      (node (ref "SW_RESET") (pin "1") (pinfunction "1_1") (pintype "passive"))
      (node (ref "U1") (pin "7") (pinfunction "~{RST}_7") (pintype "passive"))
    )
    (net (code "77") (name "Net-(U2A-CPOUT)") (class "Default")
      (node (ref "C7") (pin "1") (pinfunction "1_1") (pintype "passive"))
      (node (ref "U2") (pin "20") (pinfunction "CPOUT_20") (pintype "passive"))
    )
    (net (code "78") (name "Net-(U2A-REGOUT)") (class "Default")
      (node (ref "C8") (pin "1") (pinfunction "1_1") (pintype "passive"))
      (node (ref "U2") (pin "10") (pinfunction "REGOUT_10") (pintype "passive"))
    )
    (net (code "79") (name "Net-(U7-VOUT)") (class "Default")
      (node (ref "C100") (pin "2") (pinfunction "2_2") (pintype "passive"))
      (node (ref "C50") (pin "2") (pinfunction "2_2") (pintype "passive"))
      (node (ref "C70") (pin "2") (pinfunction "2_2") (pintype "passive"))
      (node (ref "R30") (pin "2") (pinfunction "2_2") (pintype "passive"))
      (node (ref "R40") (pin "2") (pinfunction "2_2") (pintype "passive"))
      (node (ref "R60") (pin "2") (pinfunction "2_2") (pintype "passive"))
      (node (ref "U7") (pin "1") (pinfunction "VOUT_1") (pintype "power_in"))
      (node (ref "U8") (pin "21") (pinfunction "AVDD_21") (pintype "power_in"))
      (node (ref "U8") (pin "24") (pinfunction "PVDD_24") (pintype "power_in"))
      (node (ref "U8") (pin "3") (pinfunction "DVDD_3") (pintype "power_in"))
    )
    (net (code "80") (name "Net-(U8-LOS)") (class "Default")
      (node (ref "R30") (pin "1") (pinfunction "1_1") (pintype "passive"))
      (node (ref "U8") (pin "12") (pinfunction "LOS_12") (pintype "input"))
    )
    (net (code "81") (name "Net-(U8-SAG)") (class "Default")
      (node (ref "C10") (pin "1") (pinfunction "1_1") (pintype "passive"))
      (node (ref "U8") (pin "25") (pinfunction "SAG_25") (pintype "output"))
    )
    (net (code "82") (name "Net-(U8-VIN)") (class "Default")
      (node (ref "C110") (pin "1") (pinfunction "1_1") (pintype "passive"))
      (node (ref "U8") (pin "22") (pinfunction "VIN_22") (pintype "input"))
    )
    (net (code "83") (name "Net-(U8-VOUT)") (class "Default")
      (node (ref "C90") (pin "1") (pinfunction "1_1") (pintype "passive"))
      (node (ref "U8") (pin "26") (pinfunction "VOUT_26") (pintype "output"))
    )
    (net (code "84") (name "Net-(U8-~{RESET})") (class "Default")
      (node (ref "R50") (pin "1") (pinfunction "1_1") (pintype "passive"))
      (node (ref "U8") (pin "19") (pinfunction "~{RESET}_19") (pintype "input"))
    )
    (net (code "85") (name "unconnected-(C20-Pad1)") (class "Default")
      (node (ref "C20") (pin "1") (pinfunction "1_1") (pintype "passive"))
    )
    (net (code "86") (name "unconnected-(CD1-DAT1-Pad8)") (class "Default")
      (node (ref "CD1") (pin "8") (pinfunction "DAT1_8") (pintype "passive"))
    )
    (net (code "87") (name "unconnected-(CD1-DAT2-Pad1)") (class "Default")
      (node (ref "CD1") (pin "1") (pinfunction "DAT2_1") (pintype "passive"))
    )
    (net (code "88") (name "unconnected-(CD1-DETECT-Pad9)") (class "Default")
      (node (ref "CD1") (pin "9") (pinfunction "DETECT_9") (pintype "passive"))
    )
    (net (code "89") (name "unconnected-(CD1-SWITCH-Pad10)") (class "Default")
      (node (ref "CD1") (pin "10") (pinfunction "SWITCH_10") (pintype "passive"))
    )
    (net (code "90") (name "unconnected-(J1-ID-Pad4)") (class "Default")
      (node (ref "J1") (pin "4") (pinfunction "ID_4") (pintype "passive"))
    )
    (net (code "91") (name "unconnected-(U1B-VDD-Pad19)") (class "Default")
      (node (ref "U1") (pin "19") (pinfunction "VDD_19") (pintype "passive"))
    )
    (net (code "92") (name "unconnected-(U2A-AUX_CL-Pad7)") (class "Default")
      (node (ref "U2") (pin "7") (pinfunction "AUX_CL_7") (pintype "output"))
    )
    (net (code "93") (name "unconnected-(U2A-AUX_DA-Pad6)") (class "Default")
      (node (ref "U2") (pin "6") (pinfunction "AUX_DA_6") (pintype "bidirectional"))
    )
    (net (code "94") (name "unconnected-(U2A-EP-Pad25)") (class "Default")
      (node (ref "U2") (pin "25") (pinfunction "EP_25") (pintype "passive"))
    )
    (net (code "95") (name "unconnected-(U2A-RESV-Pad19)") (class "Default")
      (node (ref "U2") (pin "19") (pinfunction "RESV_19") (pintype "passive"))
    )
    (net (code "96") (name "unconnected-(U2A-RESV-Pad21)") (class "Default")
      (node (ref "U2") (pin "21") (pinfunction "RESV_21") (pintype "passive"))
    )
    (net (code "97") (name "unconnected-(U2A-RESV-Pad22)") (class "Default")
      (node (ref "U2") (pin "22") (pinfunction "RESV_22") (pintype "passive"))
    )
    (net (code "98") (name "unconnected-(U2B-NC-Pad2)") (class "Default")
      (node (ref "U2") (pin "2") (pinfunction "NC_2") (pintype "passive"))
    )
    (net (code "99") (name "unconnected-(U2B-NC-Pad3)") (class "Default")
      (node (ref "U2") (pin "3") (pinfunction "NC_3") (pintype "passive"))
    )
    (net (code "100") (name "unconnected-(U2B-NC-Pad4)") (class "Default")
      (node (ref "U2") (pin "4") (pinfunction "NC_4") (pintype "passive"))
    )
    (net (code "101") (name "unconnected-(U2B-NC-Pad5)") (class "Default")
      (node (ref "U2") (pin "5") (pinfunction "NC_5") (pintype "passive"))
    )
    (net (code "102") (name "unconnected-(U2B-NC-Pad14)") (class "Default")
      (node (ref "U2") (pin "14") (pinfunction "NC_14") (pintype "passive"))
    )
    (net (code "103") (name "unconnected-(U2B-NC-Pad15)") (class "Default")
      (node (ref "U2") (pin "15") (pinfunction "NC_15") (pintype "passive"))
    )
    (net (code "104") (name "unconnected-(U2B-NC-Pad16)") (class "Default")
      (node (ref "U2") (pin "16") (pinfunction "NC_16") (pintype "passive"))
    )
    (net (code "105") (name "unconnected-(U2B-NC-Pad17)") (class "Default")
      (node (ref "U2") (pin "17") (pinfunction "NC_17") (pintype "passive"))
    )
    (net (code "106") (name "unconnected-(U3-VDDIO-Pad6)") (class "Default")
      (node (ref "U3") (pin "6") (pinfunction "VDDIO_6") (pintype "power_in"))
    )
    (net (code "107") (name "unconnected-(U4-TAB-Pad4)") (class "Default")
      (node (ref "U4") (pin "4") (pinfunction "TAB_4") (pintype "power_in"))
    )
    (net (code "108") (name "unconnected-(U6-TAB-Pad4)") (class "Default")
      (node (ref "U6") (pin "4") (pinfunction "TAB_4") (pintype "passive"))
    )
    (net (code "109") (name "unconnected-(U8-EP-Pad29)") (class "Default")
      (node (ref "U8") (pin "29") (pinfunction "EP_29") (pintype "power_in"))
    )
    (net (code "110") (name "unconnected-(U8-NC-Pad1)") (class "Default")
      (node (ref "U8") (pin "1") (pinfunction "NC_1") (pintype "passive"))
    )
    (net (code "111") (name "unconnected-(U8-NC-Pad2)") (class "Default")
      (node (ref "U8") (pin "2") (pinfunction "NC_2") (pintype "passive"))
    )
    (net (code "112") (name "unconnected-(U8-NC-Pad13)") (class "Default")
      (node (ref "U8") (pin "13") (pinfunction "NC_13") (pintype "passive"))
    )
    (net (code "113") (name "unconnected-(U8-NC-Pad14)") (class "Default")
      (node (ref "U8") (pin "14") (pinfunction "NC_14") (pintype "passive"))
    )
    (net (code "114") (name "unconnected-(U8-NC-Pad15)") (class "Default")
      (node (ref "U8") (pin "15") (pinfunction "NC_15") (pintype "passive"))
    )
    (net (code "115") (name "unconnected-(U8-NC-Pad16)") (class "Default")
      (node (ref "U8") (pin "16") (pinfunction "NC_16") (pintype "passive"))
    )
    (net (code "116") (name "unconnected-(U8-NC-Pad27)") (class "Default")
      (node (ref "U8") (pin "27") (pinfunction "NC_27") (pintype "passive"))
    )
    (net (code "117") (name "unconnected-(U8-NC-Pad28)") (class "Default")
      (node (ref "U8") (pin "28") (pinfunction "NC_28") (pintype "passive"))
    )
  )
)
